# S7CAS-PLEIADES-CARTE-MERE_P06_DAC.net
KiCad netlist of a schematic drawn in Altium Designer
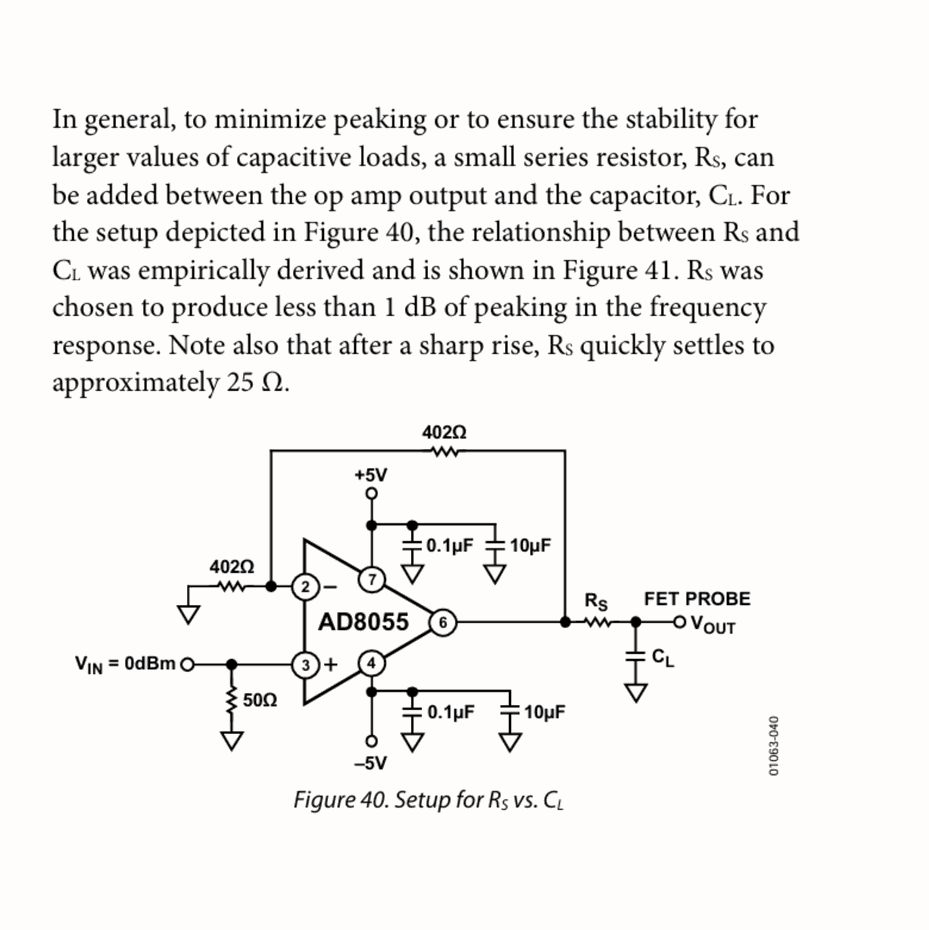
[diagram p0: S7CAS-PLEIADES-CARTE-MERE_P06_DAC.SchDoc, left]
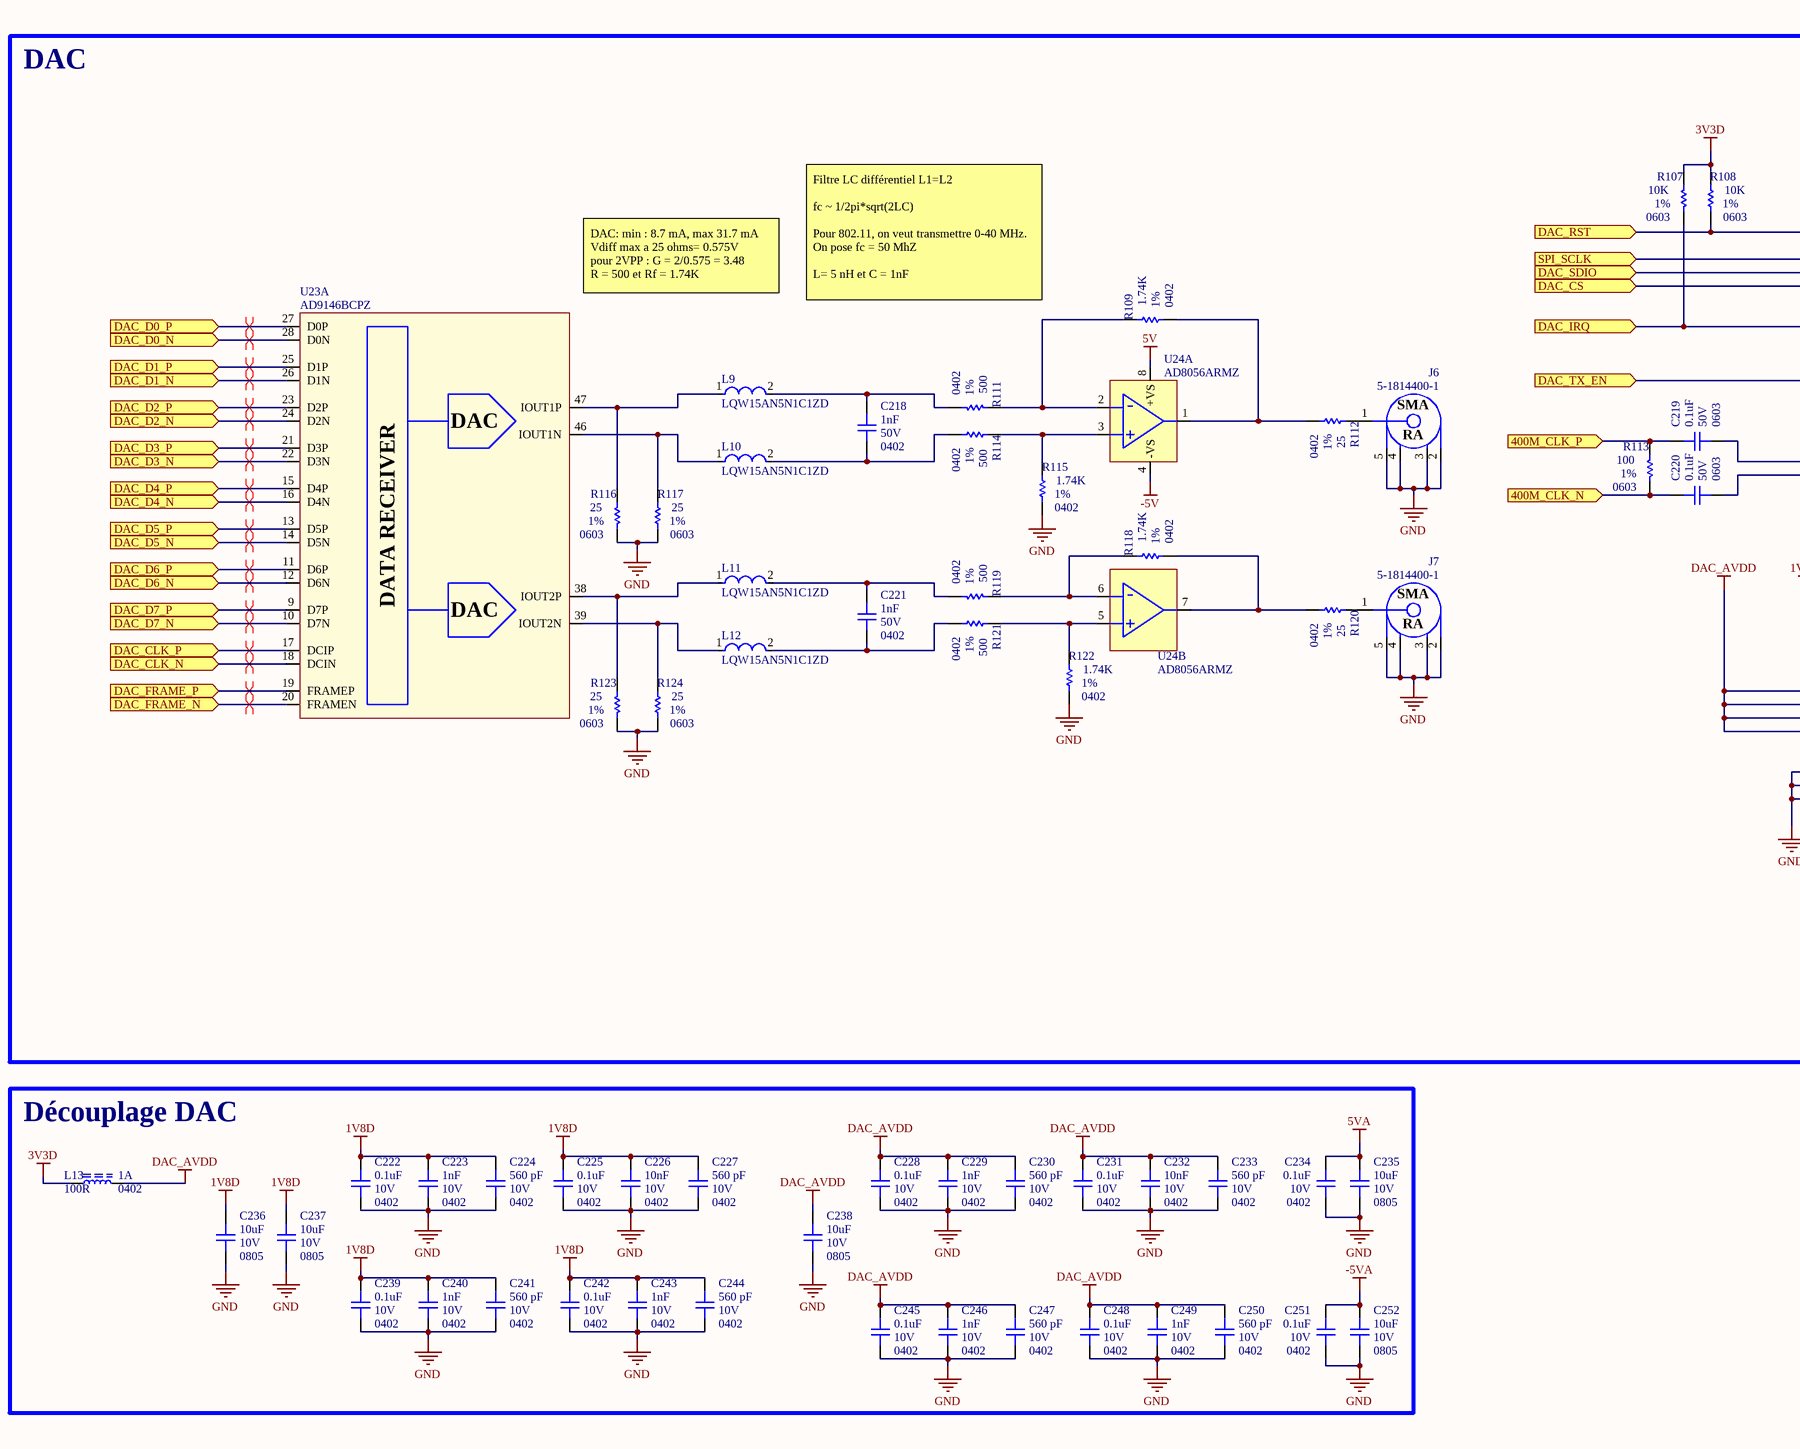
[diagram p1: S7CAS-PLEIADES-CARTE-MERE_P06_DAC.SchDoc, middle]
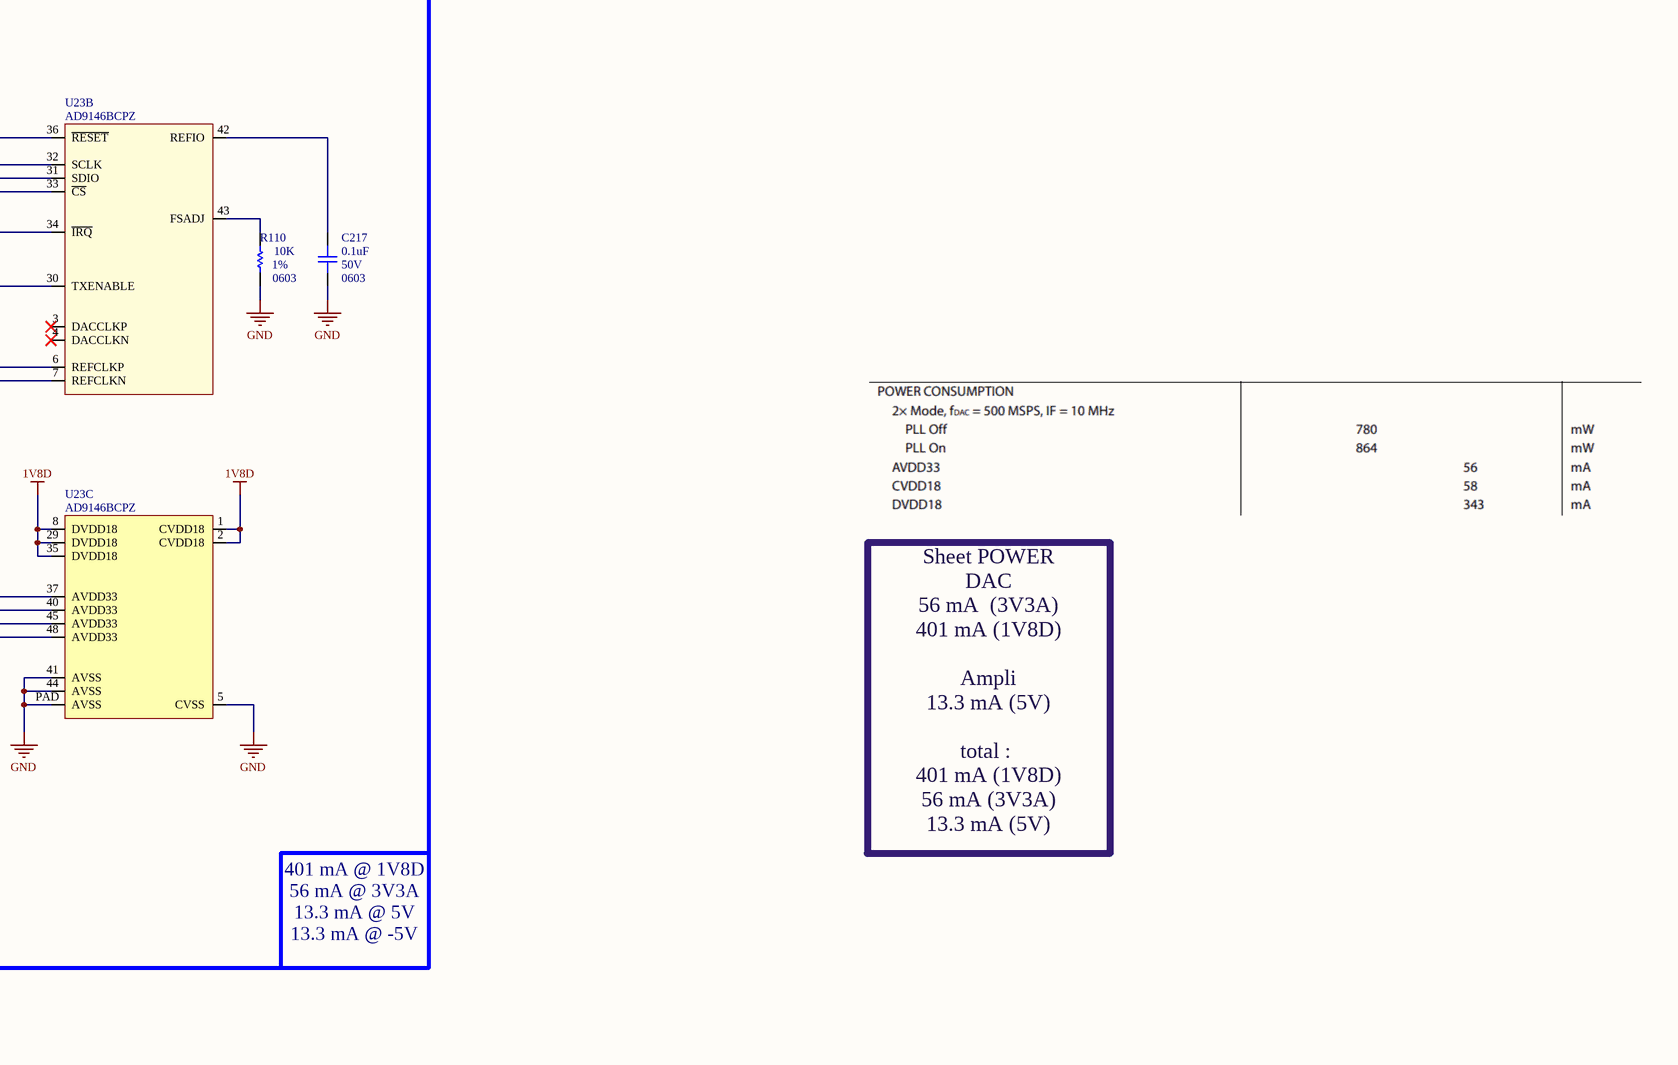
[diagram p2: S7CAS-PLEIADES-CARTE-MERE_P06_DAC.SchDoc, right]

(export (version "E")
  (design (tool "Eeschema 10.0.6"))
  (components
    (comp (ref "C217")
      (value "0.1uF")
      (footprint "CAP_0603")
      (description "CAP - 0603")
      (fields
        (field (name "VOLTAGE") "50V")
        (field (name "PACKAGE") "0603")
        (field (name "CREATEDBY") "Jonathan Bouchard")
      )
      (libsource (lib "s7cas_lib2023") (part "CAP - 0603"))
    )
    (comp (ref "C218")
      (value "1nF")
      (footprint "CAP_0402")
      (description "CAP - 0402")
      (fields
        (field (name "MFG PART NUMBER") "GCM1555C1H102FA16D")
        (field (name "VOLTAGE") "50V")
        (field (name "PACKAGE") "0402")
        (field (name "CREATEDBY") "Jonathan Bouchard")
      )
      (libsource (lib "s7cas_lib2023") (part "CAP - 0402"))
    )
    (comp (ref "C219")
      (value "0.1uF")
      (footprint "CAP_0603")
      (description "CAP - 0603")
      (fields
        (field (name "VOLTAGE") "50V")
        (field (name "PACKAGE") "0603")
        (field (name "CREATEDBY") "Jonathan Bouchard")
      )
      (libsource (lib "s7cas_lib2023") (part "CAP - 0603"))
    )
    (comp (ref "C220")
      (value "0.1uF")
      (footprint "CAP_0603")
      (description "CAP - 0603")
      (fields
        (field (name "VOLTAGE") "50V")
        (field (name "PACKAGE") "0603")
        (field (name "CREATEDBY") "Jonathan Bouchard")
      )
      (libsource (lib "s7cas_lib2023") (part "CAP - 0603"))
    )
    (comp (ref "C221")
      (value "1nF")
      (footprint "CAP_0402")
      (description "CAP - 0402")
      (fields
        (field (name "MFG PART NUMBER") "GCM1555C1H102FA16D")
        (field (name "VOLTAGE") "50V")
        (field (name "PACKAGE") "0402")
        (field (name "CREATEDBY") "Jonathan Bouchard")
      )
      (libsource (lib "s7cas_lib2023") (part "CAP - 0402"))
    )
    (comp (ref "C222")
      (value "0.1uF")
      (footprint "CAP_0402")
      (description "CAP - 0402")
      (fields
        (field (name "VOLTAGE") "10V")
        (field (name "PACKAGE") "0402")
        (field (name "CREATEDBY") "Jonathan Bouchard")
      )
      (libsource (lib "s7cas_lib2023") (part "CAP - 0402"))
    )
    (comp (ref "C223")
      (value "1nF")
      (footprint "CAP_0402")
      (description "CAP - 0402")
      (fields
        (field (name "VOLTAGE") "10V")
        (field (name "PACKAGE") "0402")
        (field (name "CREATEDBY") "Jonathan Bouchard")
      )
      (libsource (lib "s7cas_lib2023") (part "CAP - 0402"))
    )
    (comp (ref "C224")
      (value "560 pF")
      (footprint "CAP_0402")
      (description "CAP - 0402")
      (fields
        (field (name "VOLTAGE") "10V")
        (field (name "PACKAGE") "0402")
        (field (name "CREATEDBY") "Jonathan Bouchard")
      )
      (libsource (lib "s7cas_lib2023") (part "CAP - 0402"))
    )
    (comp (ref "C225")
      (value "0.1uF")
      (footprint "CAP_0402")
      (description "CAP - 0402")
      (fields
        (field (name "VOLTAGE") "10V")
        (field (name "PACKAGE") "0402")
        (field (name "CREATEDBY") "Jonathan Bouchard")
      )
      (libsource (lib "s7cas_lib2023") (part "CAP - 0402"))
    )
    (comp (ref "C226")
      (value "10nF")
      (footprint "CAP_0402")
      (description "CAP - 0402")
      (fields
        (field (name "VOLTAGE") "10V")
        (field (name "PACKAGE") "0402")
        (field (name "CREATEDBY") "Jonathan Bouchard")
      )
      (libsource (lib "s7cas_lib2023") (part "CAP - 0402"))
    )
    (comp (ref "C227")
      (value "560 pF")
      (footprint "CAP_0402")
      (description "CAP - 0402")
      (fields
        (field (name "VOLTAGE") "10V")
        (field (name "PACKAGE") "0402")
        (field (name "CREATEDBY") "Jonathan Bouchard")
      )
      (libsource (lib "s7cas_lib2023") (part "CAP - 0402"))
    )
    (comp (ref "C228")
      (value "0.1uF")
      (footprint "CAP_0402")
      (description "CAP - 0402")
      (fields
        (field (name "VOLTAGE") "10V")
        (field (name "PACKAGE") "0402")
        (field (name "CREATEDBY") "Jonathan Bouchard")
      )
      (libsource (lib "s7cas_lib2023") (part "CAP - 0402"))
    )
    (comp (ref "C229")
      (value "1nF")
      (footprint "CAP_0402")
      (description "CAP - 0402")
      (fields
        (field (name "VOLTAGE") "10V")
        (field (name "PACKAGE") "0402")
        (field (name "CREATEDBY") "Jonathan Bouchard")
      )
      (libsource (lib "s7cas_lib2023") (part "CAP - 0402"))
    )
    (comp (ref "C230")
      (value "560 pF")
      (footprint "CAP_0402")
      (description "CAP - 0402")
      (fields
        (field (name "VOLTAGE") "10V")
        (field (name "PACKAGE") "0402")
        (field (name "CREATEDBY") "Jonathan Bouchard")
      )
      (libsource (lib "s7cas_lib2023") (part "CAP - 0402"))
    )
    (comp (ref "C231")
      (value "0.1uF")
      (footprint "CAP_0402")
      (description "CAP - 0402")
      (fields
        (field (name "VOLTAGE") "10V")
        (field (name "PACKAGE") "0402")
        (field (name "CREATEDBY") "Jonathan Bouchard")
      )
      (libsource (lib "s7cas_lib2023") (part "CAP - 0402"))
    )
    (comp (ref "C232")
      (value "10nF")
      (footprint "CAP_0402")
      (description "CAP - 0402")
      (fields
        (field (name "VOLTAGE") "10V")
        (field (name "PACKAGE") "0402")
        (field (name "CREATEDBY") "Jonathan Bouchard")
      )
      (libsource (lib "s7cas_lib2023") (part "CAP - 0402"))
    )
    (comp (ref "C233")
      (value "560 pF")
      (footprint "CAP_0402")
      (description "CAP - 0402")
      (fields
        (field (name "VOLTAGE") "10V")
        (field (name "PACKAGE") "0402")
        (field (name "CREATEDBY") "Jonathan Bouchard")
      )
      (libsource (lib "s7cas_lib2023") (part "CAP - 0402"))
    )
    (comp (ref "C234")
      (value "0.1uF")
      (footprint "CAP_0402")
      (description "CAP - 0402")
      (fields
        (field (name "VOLTAGE") "10V")
        (field (name "PACKAGE") "0402")
        (field (name "CREATEDBY") "Jonathan Bouchard")
      )
      (libsource (lib "s7cas_lib2023") (part "CAP - 0402"))
    )
    (comp (ref "C235")
      (value "10uF")
      (footprint "CAP_0805")
      (description "CAP - 0805")
      (fields
        (field (name "VOLTAGE") "10V")
        (field (name "PACKAGE") "0805")
        (field (name "CREATEDBY") "Jonathan Bouchard")
      )
      (libsource (lib "s7cas_lib2023") (part "CAP - 0805"))
    )
    (comp (ref "C236")
      (value "10uF")
      (footprint "CAP_0805")
      (description "CAP - 0805")
      (fields
        (field (name "VOLTAGE") "10V")
        (field (name "PACKAGE") "0805")
        (field (name "CREATEDBY") "Jonathan Bouchard")
      )
      (libsource (lib "s7cas_lib2023") (part "CAP - 0805"))
    )
    (comp (ref "C237")
      (value "10uF")
      (footprint "CAP_0805")
      (description "CAP - 0805")
      (fields
        (field (name "VOLTAGE") "10V")
        (field (name "PACKAGE") "0805")
        (field (name "CREATEDBY") "Jonathan Bouchard")
      )
      (libsource (lib "s7cas_lib2023") (part "CAP - 0805"))
    )
    (comp (ref "C238")
      (value "10uF")
      (footprint "CAP_0805")
      (description "CAP - 0805")
      (fields
        (field (name "VOLTAGE") "10V")
        (field (name "PACKAGE") "0805")
        (field (name "CREATEDBY") "Jonathan Bouchard")
      )
      (libsource (lib "s7cas_lib2023") (part "CAP - 0805"))
    )
    (comp (ref "C239")
      (value "0.1uF")
      (footprint "CAP_0402")
      (description "CAP - 0402")
      (fields
        (field (name "VOLTAGE") "10V")
        (field (name "PACKAGE") "0402")
        (field (name "CREATEDBY") "Jonathan Bouchard")
      )
      (libsource (lib "s7cas_lib2023") (part "CAP - 0402"))
    )
    (comp (ref "C240")
      (value "1nF")
      (footprint "CAP_0402")
      (description "CAP - 0402")
      (fields
        (field (name "VOLTAGE") "10V")
        (field (name "PACKAGE") "0402")
        (field (name "CREATEDBY") "Jonathan Bouchard")
      )
      (libsource (lib "s7cas_lib2023") (part "CAP - 0402"))
    )
    (comp (ref "C241")
      (value "560 pF")
      (footprint "CAP_0402")
      (description "CAP - 0402")
      (fields
        (field (name "VOLTAGE") "10V")
        (field (name "PACKAGE") "0402")
        (field (name "CREATEDBY") "Jonathan Bouchard")
      )
      (libsource (lib "s7cas_lib2023") (part "CAP - 0402"))
    )
    (comp (ref "C242")
      (value "0.1uF")
      (footprint "CAP_0402")
      (description "CAP - 0402")
      (fields
        (field (name "VOLTAGE") "10V")
        (field (name "PACKAGE") "0402")
        (field (name "CREATEDBY") "Jonathan Bouchard")
      )
      (libsource (lib "s7cas_lib2023") (part "CAP - 0402"))
    )
    (comp (ref "C243")
      (value "1nF")
      (footprint "CAP_0402")
      (description "CAP - 0402")
      (fields
        (field (name "VOLTAGE") "10V")
        (field (name "PACKAGE") "0402")
        (field (name "CREATEDBY") "Jonathan Bouchard")
      )
      (libsource (lib "s7cas_lib2023") (part "CAP - 0402"))
    )
    (comp (ref "C244")
      (value "560 pF")
      (footprint "CAP_0402")
      (description "CAP - 0402")
      (fields
        (field (name "VOLTAGE") "10V")
        (field (name "PACKAGE") "0402")
        (field (name "CREATEDBY") "Jonathan Bouchard")
      )
      (libsource (lib "s7cas_lib2023") (part "CAP - 0402"))
    )
    (comp (ref "C245")
      (value "0.1uF")
      (footprint "CAP_0402")
      (description "CAP - 0402")
      (fields
        (field (name "VOLTAGE") "10V")
        (field (name "PACKAGE") "0402")
        (field (name "CREATEDBY") "Jonathan Bouchard")
      )
      (libsource (lib "s7cas_lib2023") (part "CAP - 0402"))
    )
    (comp (ref "C246")
      (value "1nF")
      (footprint "CAP_0402")
      (description "CAP - 0402")
      (fields
        (field (name "VOLTAGE") "10V")
        (field (name "PACKAGE") "0402")
        (field (name "CREATEDBY") "Jonathan Bouchard")
      )
      (libsource (lib "s7cas_lib2023") (part "CAP - 0402"))
    )
    (comp (ref "C247")
      (value "560 pF")
      (footprint "CAP_0402")
      (description "CAP - 0402")
      (fields
        (field (name "VOLTAGE") "10V")
        (field (name "PACKAGE") "0402")
        (field (name "CREATEDBY") "Jonathan Bouchard")
      )
      (libsource (lib "s7cas_lib2023") (part "CAP - 0402"))
    )
    (comp (ref "C248")
      (value "0.1uF")
      (footprint "CAP_0402")
      (description "CAP - 0402")
      (fields
        (field (name "VOLTAGE") "10V")
        (field (name "PACKAGE") "0402")
        (field (name "CREATEDBY") "Jonathan Bouchard")
      )
      (libsource (lib "s7cas_lib2023") (part "CAP - 0402"))
    )
    (comp (ref "C249")
      (value "1nF")
      (footprint "CAP_0402")
      (description "CAP - 0402")
      (fields
        (field (name "VOLTAGE") "10V")
        (field (name "PACKAGE") "0402")
        (field (name "CREATEDBY") "Jonathan Bouchard")
      )
      (libsource (lib "s7cas_lib2023") (part "CAP - 0402"))
    )
    (comp (ref "C250")
      (value "560 pF")
      (footprint "CAP_0402")
      (description "CAP - 0402")
      (fields
        (field (name "VOLTAGE") "10V")
        (field (name "PACKAGE") "0402")
        (field (name "CREATEDBY") "Jonathan Bouchard")
      )
      (libsource (lib "s7cas_lib2023") (part "CAP - 0402"))
    )
    (comp (ref "C251")
      (value "0.1uF")
      (footprint "CAP_0402")
      (description "CAP - 0402")
      (fields
        (field (name "VOLTAGE") "10V")
        (field (name "PACKAGE") "0402")
        (field (name "CREATEDBY") "Jonathan Bouchard")
      )
      (libsource (lib "s7cas_lib2023") (part "CAP - 0402"))
    )
    (comp (ref "C252")
      (value "10uF")
      (footprint "CAP_0805")
      (description "CAP - 0805")
      (fields
        (field (name "VOLTAGE") "10V")
        (field (name "PACKAGE") "0805")
        (field (name "CREATEDBY") "Jonathan Bouchard")
      )
      (libsource (lib "s7cas_lib2023") (part "CAP - 0805"))
    )
    (comp (ref "J6")
      (value "5-1814400-1")
      (footprint "CONN_SMA_5-1814400-1")
      (description "CONN -  SMA JACK R/A 50 OHM - TH")
      (fields
        (field (name "MFG") "TE Connectivity AMP Connectors")
        (field (name "CREATEDBY") "Jonathan Bouchard")
      )
      (libsource (lib "s7cas_lib2023") (part "CONN_SMA_5-1814400-1"))
    )
    (comp (ref "J7")
      (value "5-1814400-1")
      (footprint "CONN_SMA_5-1814400-1")
      (description "CONN -  SMA JACK R/A 50 OHM - TH")
      (fields
        (field (name "MFG") "TE Connectivity AMP Connectors")
        (field (name "CREATEDBY") "Jonathan Bouchard")
      )
      (libsource (lib "s7cas_lib2023") (part "CONN_SMA_5-1814400-1"))
    )
    (comp (ref "L9")
      (value "LQW15AN5N1C1ZD")
      (footprint "FP-LQW15AN_00-W0_6-0_1-MFG")
      (description "Wire Wound RF Inductor for Automotive 5.1nH ±0.2nH 800mA 0.051Ω 0402 (1005)")
      (libsource (lib "Altium Content Vault") (part "725321dda6339637d4d059423bc1c3c"))
    )
    (comp (ref "L10")
      (value "LQW15AN5N1C1ZD")
      (footprint "FP-LQW15AN_00-W0_6-0_1-MFG")
      (description "Wire Wound RF Inductor for Automotive 5.1nH ±0.2nH 800mA 0.051Ω 0402 (1005)")
      (libsource (lib "Altium Content Vault") (part "725321dda6339637d4d059423bc1c3c"))
    )
    (comp (ref "L11")
      (value "LQW15AN5N1C1ZD")
      (footprint "FP-LQW15AN_00-W0_6-0_1-MFG")
      (description "Wire Wound RF Inductor for Automotive 5.1nH ±0.2nH 800mA 0.051Ω 0402 (1005)")
      (libsource (lib "Altium Content Vault") (part "725321dda6339637d4d059423bc1c3c"))
    )
    (comp (ref "L12")
      (value "LQW15AN5N1C1ZD")
      (footprint "FP-LQW15AN_00-W0_6-0_1-MFG")
      (description "Wire Wound RF Inductor for Automotive 5.1nH ±0.2nH 800mA 0.051Ω 0402 (1005)")
      (libsource (lib "Altium Content Vault") (part "725321dda6339637d4d059423bc1c3c"))
    )
    (comp (ref "L13")
      (value "100R")
      (footprint "FER_0402")
      (description "FER - 0402")
      (fields
        (field (name "CURRENT") "1A")
        (field (name "PACKAGE") "0402")
        (field (name "CREATEDBY") "Jonathan Bouchard")
      )
      (libsource (lib "s7cas_lib2023") (part "FER - 0402"))
    )
    (comp (ref "R107")
      (value "10K")
      (footprint "RES_0603")
      (description "RES - 0603")
      (fields
        (field (name "PACKAGE") "0603")
        (field (name "PRECISION") "1%")
        (field (name "CREATEDBY") "Jonathan Bouchard")
      )
      (libsource (lib "s7cas_lib2023") (part "RES - 0603"))
    )
    (comp (ref "R108")
      (value "10K")
      (footprint "RES_0603")
      (description "RES - 0603")
      (fields
        (field (name "PACKAGE") "0603")
        (field (name "PRECISION") "1%")
        (field (name "CREATEDBY") "Jonathan Bouchard")
      )
      (libsource (lib "s7cas_lib2023") (part "RES - 0603"))
    )
    (comp (ref "R109")
      (value "1.74K")
      (footprint "RES_0402")
      (description "RES - 0402")
      (fields
        (field (name "VOLTAGE") "50V")
        (field (name "POWER") "1/16W")
        (field (name "PACKAGE") "0402")
        (field (name "PRECISION") "1%")
        (field (name "CREATEDBY") "Jonathan Bouchard")
      )
      (libsource (lib "s7cas_lib2023") (part "RES - 0402"))
    )
    (comp (ref "R110")
      (value "10K")
      (footprint "RES_0603")
      (description "RES - 0603")
      (fields
        (field (name "PACKAGE") "0603")
        (field (name "PRECISION") "1%")
        (field (name "CREATEDBY") "Jonathan Bouchard")
      )
      (libsource (lib "s7cas_lib2023") (part "RES - 0603"))
    )
    (comp (ref "R111")
      (value "500")
      (footprint "RES_0402")
      (description "RES - 0402")
      (fields
        (field (name "VOLTAGE") "50V")
        (field (name "POWER") "1/16W")
        (field (name "PACKAGE") "0402")
        (field (name "PRECISION") "1%")
        (field (name "CREATEDBY") "Jonathan Bouchard")
      )
      (libsource (lib "s7cas_lib2023") (part "RES - 0402"))
    )
    (comp (ref "R112")
      (value "25")
      (footprint "RES_0402")
      (description "RES - 0402")
      (fields
        (field (name "VOLTAGE") "50V")
        (field (name "POWER") "1/16W")
        (field (name "PACKAGE") "0402")
        (field (name "PRECISION") "1%")
        (field (name "CREATEDBY") "Jonathan Bouchard")
      )
      (libsource (lib "s7cas_lib2023") (part "RES - 0402"))
    )
    (comp (ref "R113")
      (value "100")
      (footprint "RES_0603")
      (description "RES - 0603")
      (fields
        (field (name "PACKAGE") "0603")
        (field (name "PRECISION") "1%")
        (field (name "CREATEDBY") "Jonathan Bouchard")
      )
      (libsource (lib "s7cas_lib2023") (part "RES - 0603"))
    )
    (comp (ref "R114")
      (value "500")
      (footprint "RES_0402")
      (description "RES - 0402")
      (fields
        (field (name "VOLTAGE") "50V")
        (field (name "POWER") "1/16W")
        (field (name "PACKAGE") "0402")
        (field (name "PRECISION") "1%")
        (field (name "CREATEDBY") "Jonathan Bouchard")
      )
      (libsource (lib "s7cas_lib2023") (part "RES - 0402"))
    )
    (comp (ref "R115")
      (value "1.74K")
      (footprint "RES_0402")
      (description "RES - 0402")
      (fields
        (field (name "VOLTAGE") "50V")
        (field (name "POWER") "1/16W")
        (field (name "PACKAGE") "0402")
        (field (name "PRECISION") "1%")
        (field (name "CREATEDBY") "Jonathan Bouchard")
      )
      (libsource (lib "s7cas_lib2023") (part "RES - 0402"))
    )
    (comp (ref "R116")
      (value "25")
      (footprint "RES_0603")
      (description "RES - 0603")
      (fields
        (field (name "PACKAGE") "0603")
        (field (name "PRECISION") "1%")
        (field (name "CREATEDBY") "Jonathan Bouchard")
      )
      (libsource (lib "s7cas_lib2023") (part "RES - 0603"))
    )
    (comp (ref "R117")
      (value "25")
      (footprint "RES_0603")
      (description "RES - 0603")
      (fields
        (field (name "PACKAGE") "0603")
        (field (name "PRECISION") "1%")
        (field (name "CREATEDBY") "Jonathan Bouchard")
      )
      (libsource (lib "s7cas_lib2023") (part "RES - 0603"))
    )
    (comp (ref "R118")
      (value "1.74K")
      (footprint "RES_0402")
      (description "RES - 0402")
      (fields
        (field (name "VOLTAGE") "50V")
        (field (name "POWER") "1/16W")
        (field (name "PACKAGE") "0402")
        (field (name "PRECISION") "1%")
        (field (name "CREATEDBY") "Jonathan Bouchard")
      )
      (libsource (lib "s7cas_lib2023") (part "RES - 0402"))
    )
    (comp (ref "R119")
      (value "500")
      (footprint "RES_0402")
      (description "RES - 0402")
      (fields
        (field (name "VOLTAGE") "50V")
        (field (name "POWER") "1/16W")
        (field (name "PACKAGE") "0402")
        (field (name "PRECISION") "1%")
        (field (name "CREATEDBY") "Jonathan Bouchard")
      )
      (libsource (lib "s7cas_lib2023") (part "RES - 0402"))
    )
    (comp (ref "R120")
      (value "25")
      (footprint "RES_0402")
      (description "RES - 0402")
      (fields
        (field (name "VOLTAGE") "50V")
        (field (name "POWER") "1/16W")
        (field (name "PACKAGE") "0402")
        (field (name "PRECISION") "1%")
        (field (name "CREATEDBY") "Jonathan Bouchard")
      )
      (libsource (lib "s7cas_lib2023") (part "RES - 0402"))
    )
    (comp (ref "R121")
      (value "500")
      (footprint "RES_0402")
      (description "RES - 0402")
      (fields
        (field (name "VOLTAGE") "50V")
        (field (name "POWER") "1/16W")
        (field (name "PACKAGE") "0402")
        (field (name "PRECISION") "1%")
        (field (name "CREATEDBY") "Jonathan Bouchard")
      )
      (libsource (lib "s7cas_lib2023") (part "RES - 0402"))
    )
    (comp (ref "R122")
      (value "1.74K")
      (footprint "RES_0402")
      (description "RES - 0402")
      (fields
        (field (name "VOLTAGE") "50V")
        (field (name "POWER") "1/16W")
        (field (name "PACKAGE") "0402")
        (field (name "PRECISION") "1%")
        (field (name "CREATEDBY") "Jonathan Bouchard")
      )
      (libsource (lib "s7cas_lib2023") (part "RES - 0402"))
    )
    (comp (ref "R123")
      (value "25")
      (footprint "RES_0603")
      (description "RES - 0603")
      (fields
        (field (name "PACKAGE") "0603")
        (field (name "PRECISION") "1%")
        (field (name "CREATEDBY") "Jonathan Bouchard")
      )
      (libsource (lib "s7cas_lib2023") (part "RES - 0603"))
    )
    (comp (ref "R124")
      (value "25")
      (footprint "RES_0603")
      (description "RES - 0603")
      (fields
        (field (name "PACKAGE") "0603")
        (field (name "PRECISION") "1%")
        (field (name "CREATEDBY") "Jonathan Bouchard")
      )
      (libsource (lib "s7cas_lib2023") (part "RES - 0603"))
    )
    (comp (ref "U23")
      (value "AD9146BCPZ")
      (footprint "DAC_AD9146BCPZ")
      (description "DAC - 16BIT SRL HIGH SPEED - QFN-48")
      (fields
        (field (name "VOLTAGE") "3.13 V ~ 3.47 V / 1.71 V ~ 1.89 V")
        (field (name "MFG") "Analog Devices Inc.")
        (field (name "CREATEDBY") "Jonathan Bouchard")
      )
      (libsource (lib "s7cas_lib2023") (part "DAC_AD9146BCPZ"))
    )
    (comp (ref "U24")
      (value "AD8056ARMZ")
      (footprint "OPAMP_AD8056ARMZ")
      (description "OPAMP - VFB 300MHZ - 8MSOP")
      (fields
        (field (name "VOLTAGE") "8 V ~ 12 V, ±4 V ~ 6 V")
        (field (name "MFG") "Analog Devices")
        (field (name "CREATEDBY") "Jonathan Bouchard")
      )
      (libsource (lib "s7cas_lib2023") (part "OPAMP_AD8056ARMZ"))
    )
  )
  (nets
    (net (code "1") (name "-5V") (class "Default")
      (node (ref "U24") (pin "4") (pinfunction "-VS_4") (pintype "passive"))
    )
    (net (code "2") (name "-5VA") (class "Default")
      (node (ref "C251") (pin "2") (pinfunction "2_2") (pintype "passive"))
      (node (ref "C252") (pin "2") (pinfunction "2_2") (pintype "passive"))
    )
    (net (code "3") (name "/400M_CLK_N") (class "Default")
      (node (ref "C220") (pin "2") (pinfunction "2_2") (pintype "passive"))
      (node (ref "R113") (pin "1") (pinfunction "1_1") (pintype "passive"))
    )
    (net (code "4") (name "/400M_CLK_P") (class "Default")
      (node (ref "C219") (pin "2") (pinfunction "2_2") (pintype "passive"))
      (node (ref "R113") (pin "2") (pinfunction "2_2") (pintype "passive"))
    )
    (net (code "5") (name "/DAC_CLK_N") (class "Default")
      (node (ref "U23") (pin "18") (pinfunction "DCIN_18") (pintype "passive"))
    )
    (net (code "6") (name "/DAC_CLK_P") (class "Default")
      (node (ref "U23") (pin "17") (pinfunction "DCIP_17") (pintype "passive"))
    )
    (net (code "7") (name "/DAC_CS") (class "Default")
      (node (ref "U23") (pin "33") (pinfunction "~{CS}_33") (pintype "passive"))
    )
    (net (code "8") (name "/DAC_D0_N") (class "Default")
      (node (ref "U23") (pin "28") (pinfunction "D0N_28") (pintype "passive"))
    )
    (net (code "9") (name "/DAC_D0_P") (class "Default")
      (node (ref "U23") (pin "27") (pinfunction "D0P_27") (pintype "passive"))
    )
    (net (code "10") (name "/DAC_D1_N") (class "Default")
      (node (ref "U23") (pin "26") (pinfunction "D1N_26") (pintype "passive"))
    )
    (net (code "11") (name "/DAC_D1_P") (class "Default")
      (node (ref "U23") (pin "25") (pinfunction "D1P_25") (pintype "passive"))
    )
    (net (code "12") (name "/DAC_D2_N") (class "Default")
      (node (ref "U23") (pin "24") (pinfunction "D2N_24") (pintype "passive"))
    )
    (net (code "13") (name "/DAC_D2_P") (class "Default")
      (node (ref "U23") (pin "23") (pinfunction "D2P_23") (pintype "passive"))
    )
    (net (code "14") (name "/DAC_D3_N") (class "Default")
      (node (ref "U23") (pin "22") (pinfunction "D3N_22") (pintype "passive"))
    )
    (net (code "15") (name "/DAC_D3_P") (class "Default")
      (node (ref "U23") (pin "21") (pinfunction "D3P_21") (pintype "passive"))
    )
    (net (code "16") (name "/DAC_D4_N") (class "Default")
      (node (ref "U23") (pin "16") (pinfunction "D4N_16") (pintype "passive"))
    )
    (net (code "17") (name "/DAC_D4_P") (class "Default")
      (node (ref "U23") (pin "15") (pinfunction "D4P_15") (pintype "passive"))
    )
    (net (code "18") (name "/DAC_D5_N") (class "Default")
      (node (ref "U23") (pin "14") (pinfunction "D5N_14") (pintype "passive"))
    )
    (net (code "19") (name "/DAC_D5_P") (class "Default")
      (node (ref "U23") (pin "13") (pinfunction "D5P_13") (pintype "passive"))
    )
    (net (code "20") (name "/DAC_D6_N") (class "Default")
      (node (ref "U23") (pin "12") (pinfunction "D6N_12") (pintype "passive"))
    )
    (net (code "21") (name "/DAC_D6_P") (class "Default")
      (node (ref "U23") (pin "11") (pinfunction "D6P_11") (pintype "passive"))
    )
    (net (code "22") (name "/DAC_D7_N") (class "Default")
      (node (ref "U23") (pin "10") (pinfunction "D7N_10") (pintype "passive"))
    )
    (net (code "23") (name "/DAC_D7_P") (class "Default")
      (node (ref "U23") (pin "9") (pinfunction "D7P_9") (pintype "passive"))
    )
    (net (code "24") (name "/DAC_FRAME_N") (class "Default")
      (node (ref "U23") (pin "20") (pinfunction "FRAMEN_20") (pintype "passive"))
    )
    (net (code "25") (name "/DAC_FRAME_P") (class "Default")
      (node (ref "U23") (pin "19") (pinfunction "FRAMEP_19") (pintype "passive"))
    )
    (net (code "26") (name "/DAC_IRQ") (class "Default")
      (node (ref "R107") (pin "1") (pinfunction "1_1") (pintype "passive"))
      (node (ref "U23") (pin "34") (pinfunction "~{IRQ}_34") (pintype "passive"))
    )
    (net (code "27") (name "/DAC_RST") (class "Default")
      (node (ref "R108") (pin "1") (pinfunction "1_1") (pintype "passive"))
      (node (ref "U23") (pin "36") (pinfunction "~{RESET}_36") (pintype "passive"))
    )
    (net (code "28") (name "/DAC_SDIO") (class "Default")
      (node (ref "U23") (pin "31") (pinfunction "SDIO_31") (pintype "passive"))
    )
    (net (code "29") (name "/DAC_TX_EN") (class "Default")
      (node (ref "U23") (pin "30") (pinfunction "TXENABLE_30") (pintype "passive"))
    )
    (net (code "30") (name "/SPI_SCLK") (class "Default")
      (node (ref "U23") (pin "32") (pinfunction "SCLK_32") (pintype "passive"))
    )
    (net (code "31") (name "1V8D") (class "Default")
      (node (ref "C222") (pin "2") (pinfunction "2_2") (pintype "passive"))
      (node (ref "C223") (pin "2") (pinfunction "2_2") (pintype "passive"))
      (node (ref "C224") (pin "2") (pinfunction "2_2") (pintype "passive"))
      (node (ref "C225") (pin "2") (pinfunction "2_2") (pintype "passive"))
      (node (ref "C226") (pin "2") (pinfunction "2_2") (pintype "passive"))
      (node (ref "C227") (pin "2") (pinfunction "2_2") (pintype "passive"))
      (node (ref "C236") (pin "2") (pinfunction "2_2") (pintype "passive"))
      (node (ref "C237") (pin "2") (pinfunction "2_2") (pintype "passive"))
      (node (ref "C239") (pin "2") (pinfunction "2_2") (pintype "passive"))
      (node (ref "C240") (pin "2") (pinfunction "2_2") (pintype "passive"))
      (node (ref "C241") (pin "2") (pinfunction "2_2") (pintype "passive"))
      (node (ref "C242") (pin "2") (pinfunction "2_2") (pintype "passive"))
      (node (ref "C243") (pin "2") (pinfunction "2_2") (pintype "passive"))
      (node (ref "C244") (pin "2") (pinfunction "2_2") (pintype "passive"))
      (node (ref "U23") (pin "1") (pinfunction "CVDD18_1") (pintype "passive"))
      (node (ref "U23") (pin "2") (pinfunction "CVDD18_2") (pintype "passive"))
      (node (ref "U23") (pin "29") (pinfunction "DVDD18_29") (pintype "passive"))
      (node (ref "U23") (pin "35") (pinfunction "DVDD18_35") (pintype "passive"))
      (node (ref "U23") (pin "8") (pinfunction "DVDD18_8") (pintype "passive"))
    )
    (net (code "32") (name "3V3D") (class "Default")
      (node (ref "L13") (pin "2") (pinfunction "2_2") (pintype "passive"))
      (node (ref "R107") (pin "2") (pinfunction "2_2") (pintype "passive"))
      (node (ref "R108") (pin "2") (pinfunction "2_2") (pintype "passive"))
    )
    (net (code "33") (name "5V") (class "Default")
      (node (ref "U24") (pin "8") (pinfunction "+VS_8") (pintype "passive"))
    )
    (net (code "34") (name "5VA") (class "Default")
      (node (ref "C234") (pin "2") (pinfunction "2_2") (pintype "passive"))
      (node (ref "C235") (pin "2") (pinfunction "2_2") (pintype "passive"))
    )
    (net (code "35") (name "DAC_AVDD") (class "Default")
      (node (ref "C228") (pin "2") (pinfunction "2_2") (pintype "passive"))
      (node (ref "C229") (pin "2") (pinfunction "2_2") (pintype "passive"))
      (node (ref "C230") (pin "2") (pinfunction "2_2") (pintype "passive"))
      (node (ref "C231") (pin "2") (pinfunction "2_2") (pintype "passive"))
      (node (ref "C232") (pin "2") (pinfunction "2_2") (pintype "passive"))
      (node (ref "C233") (pin "2") (pinfunction "2_2") (pintype "passive"))
      (node (ref "C238") (pin "2") (pinfunction "2_2") (pintype "passive"))
      (node (ref "C245") (pin "2") (pinfunction "2_2") (pintype "passive"))
      (node (ref "C246") (pin "2") (pinfunction "2_2") (pintype "passive"))
      (node (ref "C247") (pin "2") (pinfunction "2_2") (pintype "passive"))
      (node (ref "C248") (pin "2") (pinfunction "2_2") (pintype "passive"))
      (node (ref "C249") (pin "2") (pinfunction "2_2") (pintype "passive"))
      (node (ref "C250") (pin "2") (pinfunction "2_2") (pintype "passive"))
      (node (ref "L13") (pin "1") (pinfunction "1_1") (pintype "passive"))
      (node (ref "U23") (pin "37") (pinfunction "AVDD33_37") (pintype "passive"))
      (node (ref "U23") (pin "40") (pinfunction "AVDD33_40") (pintype "passive"))
      (node (ref "U23") (pin "45") (pinfunction "AVDD33_45") (pintype "passive"))
      (node (ref "U23") (pin "48") (pinfunction "AVDD33_48") (pintype "passive"))
    )
    (net (code "36") (name "GND") (class "Default")
      (node (ref "C217") (pin "1") (pinfunction "1_1") (pintype "passive"))
      (node (ref "C222") (pin "1") (pinfunction "1_1") (pintype "passive"))
      (node (ref "C223") (pin "1") (pinfunction "1_1") (pintype "passive"))
      (node (ref "C224") (pin "1") (pinfunction "1_1") (pintype "passive"))
      (node (ref "C225") (pin "1") (pinfunction "1_1") (pintype "passive"))
      (node (ref "C226") (pin "1") (pinfunction "1_1") (pintype "passive"))
      (node (ref "C227") (pin "1") (pinfunction "1_1") (pintype "passive"))
      (node (ref "C228") (pin "1") (pinfunction "1_1") (pintype "passive"))
      (node (ref "C229") (pin "1") (pinfunction "1_1") (pintype "passive"))
      (node (ref "C230") (pin "1") (pinfunction "1_1") (pintype "passive"))
      (node (ref "C231") (pin "1") (pinfunction "1_1") (pintype "passive"))
      (node (ref "C232") (pin "1") (pinfunction "1_1") (pintype "passive"))
      (node (ref "C233") (pin "1") (pinfunction "1_1") (pintype "passive"))
      (node (ref "C234") (pin "1") (pinfunction "1_1") (pintype "passive"))
      (node (ref "C235") (pin "1") (pinfunction "1_1") (pintype "passive"))
      (node (ref "C236") (pin "1") (pinfunction "1_1") (pintype "passive"))
      (node (ref "C237") (pin "1") (pinfunction "1_1") (pintype "passive"))
      (node (ref "C238") (pin "1") (pinfunction "1_1") (pintype "passive"))
      (node (ref "C239") (pin "1") (pinfunction "1_1") (pintype "passive"))
      (node (ref "C240") (pin "1") (pinfunction "1_1") (pintype "passive"))
      (node (ref "C241") (pin "1") (pinfunction "1_1") (pintype "passive"))
      (node (ref "C242") (pin "1") (pinfunction "1_1") (pintype "passive"))
      (node (ref "C243") (pin "1") (pinfunction "1_1") (pintype "passive"))
      (node (ref "C244") (pin "1") (pinfunction "1_1") (pintype "passive"))
      (node (ref "C245") (pin "1") (pinfunction "1_1") (pintype "passive"))
      (node (ref "C246") (pin "1") (pinfunction "1_1") (pintype "passive"))
      (node (ref "C247") (pin "1") (pinfunction "1_1") (pintype "passive"))
      (node (ref "C248") (pin "1") (pinfunction "1_1") (pintype "passive"))
      (node (ref "C249") (pin "1") (pinfunction "1_1") (pintype "passive"))
      (node (ref "C250") (pin "1") (pinfunction "1_1") (pintype "passive"))
      (node (ref "C251") (pin "1") (pinfunction "1_1") (pintype "passive"))
      (node (ref "C252") (pin "1") (pinfunction "1_1") (pintype "passive"))
      (node (ref "J6") (pin "2") (pinfunction "2_2") (pintype "passive"))
      (node (ref "J6") (pin "3") (pinfunction "3_3") (pintype "passive"))
      (node (ref "J6") (pin "4") (pinfunction "4_4") (pintype "passive"))
      (node (ref "J6") (pin "5") (pinfunction "5_5") (pintype "passive"))
      (node (ref "J7") (pin "2") (pinfunction "2_2") (pintype "passive"))
      (node (ref "J7") (pin "3") (pinfunction "3_3") (pintype "passive"))
      (node (ref "J7") (pin "4") (pinfunction "4_4") (pintype "passive"))
      (node (ref "J7") (pin "5") (pinfunction "5_5") (pintype "passive"))
      (node (ref "R110") (pin "1") (pinfunction "1_1") (pintype "passive"))
      (node (ref "R115") (pin "1") (pinfunction "1_1") (pintype "passive"))
      (node (ref "R116") (pin "1") (pinfunction "1_1") (pintype "passive"))
      (node (ref "R117") (pin "1") (pinfunction "1_1") (pintype "passive"))
      (node (ref "R122") (pin "1") (pinfunction "1_1") (pintype "passive"))
      (node (ref "R123") (pin "1") (pinfunction "1_1") (pintype "passive"))
      (node (ref "R124") (pin "1") (pinfunction "1_1") (pintype "passive"))
      (node (ref "U23") (pin "41") (pinfunction "AVSS_41") (pintype "passive"))
      (node (ref "U23") (pin "44") (pinfunction "AVSS_44") (pintype "passive"))
      (node (ref "U23") (pin "5") (pinfunction "CVSS_5") (pintype "passive"))
      (node (ref "U23") (pin "PAD") (pinfunction "AVSS_PAD") (pintype "passive"))
    )
    (net (code "37") (name "Net-(C218-Pad1)") (class "Default")
      (node (ref "C218") (pin "1") (pinfunction "1_1") (pintype "passive"))
      (node (ref "L10") (pin "2") (pinfunction "2_2") (pintype "passive"))
      (node (ref "R114") (pin "1") (pinfunction "1_1") (pintype "passive"))
    )
    (net (code "38") (name "Net-(C218-Pad2)") (class "Default")
      (node (ref "C218") (pin "2") (pinfunction "2_2") (pintype "passive"))
      (node (ref "L9") (pin "2") (pinfunction "2_2") (pintype "passive"))
      (node (ref "R111") (pin "1") (pinfunction "1_1") (pintype "passive"))
    )
    (net (code "39") (name "Net-(C221-Pad1)") (class "Default")
      (node (ref "C221") (pin "1") (pinfunction "1_1") (pintype "passive"))
      (node (ref "L12") (pin "2") (pinfunction "2_2") (pintype "passive"))
      (node (ref "R121") (pin "1") (pinfunction "1_1") (pintype "passive"))
    )
    (net (code "40") (name "Net-(C221-Pad2)") (class "Default")
      (node (ref "C221") (pin "2") (pinfunction "2_2") (pintype "passive"))
      (node (ref "L11") (pin "2") (pinfunction "2_2") (pintype "passive"))
      (node (ref "R119") (pin "1") (pinfunction "1_1") (pintype "passive"))
    )
    (net (code "41") (name "Net-(J6-Pad1)") (class "Default")
      (node (ref "J6") (pin "1") (pinfunction "1_1") (pintype "passive"))
      (node (ref "R112") (pin "2") (pinfunction "2_2") (pintype "passive"))
    )
    (net (code "42") (name "Net-(J7-Pad1)") (class "Default")
      (node (ref "J7") (pin "1") (pinfunction "1_1") (pintype "passive"))
      (node (ref "R120") (pin "2") (pinfunction "2_2") (pintype "passive"))
    )
    (net (code "43") (name "Net-(U23A-IOUT1N)") (class "Default")
      (node (ref "L10") (pin "1") (pinfunction "1_1") (pintype "passive"))
      (node (ref "R117") (pin "2") (pinfunction "2_2") (pintype "passive"))
      (node (ref "U23") (pin "46") (pinfunction "IOUT1N_46") (pintype "passive"))
    )
    (net (code "44") (name "Net-(U23A-IOUT1P)") (class "Default")
      (node (ref "L9") (pin "1") (pinfunction "1_1") (pintype "passive"))
      (node (ref "R116") (pin "2") (pinfunction "2_2") (pintype "passive"))
      (node (ref "U23") (pin "47") (pinfunction "IOUT1P_47") (pintype "passive"))
    )
    (net (code "45") (name "Net-(U23A-IOUT2N)") (class "Default")
      (node (ref "L12") (pin "1") (pinfunction "1_1") (pintype "passive"))
      (node (ref "R124") (pin "2") (pinfunction "2_2") (pintype "passive"))
      (node (ref "U23") (pin "39") (pinfunction "IOUT2N_39") (pintype "passive"))
    )
    (net (code "46") (name "Net-(U23A-IOUT2P)") (class "Default")
      (node (ref "L11") (pin "1") (pinfunction "1_1") (pintype "passive"))
      (node (ref "R123") (pin "2") (pinfunction "2_2") (pintype "passive"))
      (node (ref "U23") (pin "38") (pinfunction "IOUT2P_38") (pintype "passive"))
    )
    (net (code "47") (name "Net-(U23B-FSADJ)") (class "Default")
      (node (ref "R110") (pin "2") (pinfunction "2_2") (pintype "passive"))
      (node (ref "U23") (pin "43") (pinfunction "FSADJ_43") (pintype "passive"))
    )
    (net (code "48") (name "Net-(U23B-REFCLKN)") (class "Default")
      (node (ref "C220") (pin "1") (pinfunction "1_1") (pintype "passive"))
      (node (ref "U23") (pin "7") (pinfunction "REFCLKN_7") (pintype "passive"))
    )
    (net (code "49") (name "Net-(U23B-REFCLKP)") (class "Default")
      (node (ref "C219") (pin "1") (pinfunction "1_1") (pintype "passive"))
      (node (ref "U23") (pin "6") (pinfunction "REFCLKP_6") (pintype "passive"))
    )
    (net (code "50") (name "Net-(U23B-REFIO)") (class "Default")
      (node (ref "C217") (pin "2") (pinfunction "2_2") (pintype "passive"))
      (node (ref "U23") (pin "42") (pinfunction "REFIO_42") (pintype "passive"))
    )
    (net (code "51") (name "Net-(U24A-+IN1)") (class "Default")
      (node (ref "R114") (pin "2") (pinfunction "2_2") (pintype "passive"))
      (node (ref "R115") (pin "2") (pinfunction "2_2") (pintype "passive"))
      (node (ref "U24") (pin "3") (pinfunction "+IN1_3") (pintype "passive"))
    )
    (net (code "52") (name "Net-(U24A--IN1)") (class "Default")
      (node (ref "R109") (pin "2") (pinfunction "2_2") (pintype "passive"))
      (node (ref "R111") (pin "2") (pinfunction "2_2") (pintype "passive"))
      (node (ref "U24") (pin "2") (pinfunction "-IN1_2") (pintype "passive"))
    )
    (net (code "53") (name "Net-(U24A-OUT1)") (class "Default")
      (node (ref "R109") (pin "1") (pinfunction "1_1") (pintype "passive"))
      (node (ref "R112") (pin "1") (pinfunction "1_1") (pintype "passive"))
      (node (ref "U24") (pin "1") (pinfunction "OUT1_1") (pintype "passive"))
    )
    (net (code "54") (name "Net-(U24B-+IN2)") (class "Default")
      (node (ref "R121") (pin "2") (pinfunction "2_2") (pintype "passive"))
      (node (ref "R122") (pin "2") (pinfunction "2_2") (pintype "passive"))
      (node (ref "U24") (pin "5") (pinfunction "+IN2_5") (pintype "passive"))
    )
    (net (code "55") (name "Net-(U24B--IN2)") (class "Default")
      (node (ref "R118") (pin "2") (pinfunction "2_2") (pintype "passive"))
      (node (ref "R119") (pin "2") (pinfunction "2_2") (pintype "passive"))
      (node (ref "U24") (pin "6") (pinfunction "-IN2_6") (pintype "passive"))
    )
    (net (code "56") (name "Net-(U24B-OUT2)") (class "Default")
      (node (ref "R118") (pin "1") (pinfunction "1_1") (pintype "passive"))
      (node (ref "R120") (pin "1") (pinfunction "1_1") (pintype "passive"))
      (node (ref "U24") (pin "7") (pinfunction "OUT2_7") (pintype "passive"))
    )
    (net (code "57") (name "unconnected-(U23B-DACCLKN-Pad4)") (class "Default")
      (node (ref "U23") (pin "4") (pinfunction "DACCLKN_4") (pintype "passive+no_connect"))
    )
    (net (code "58") (name "unconnected-(U23B-DACCLKP-Pad3)") (class "Default")
      (node (ref "U23") (pin "3") (pinfunction "DACCLKP_3") (pintype "passive+no_connect"))
    )
  )
)
